# RD.net
KiCad netlist of a schematic drawn in Altium Designer
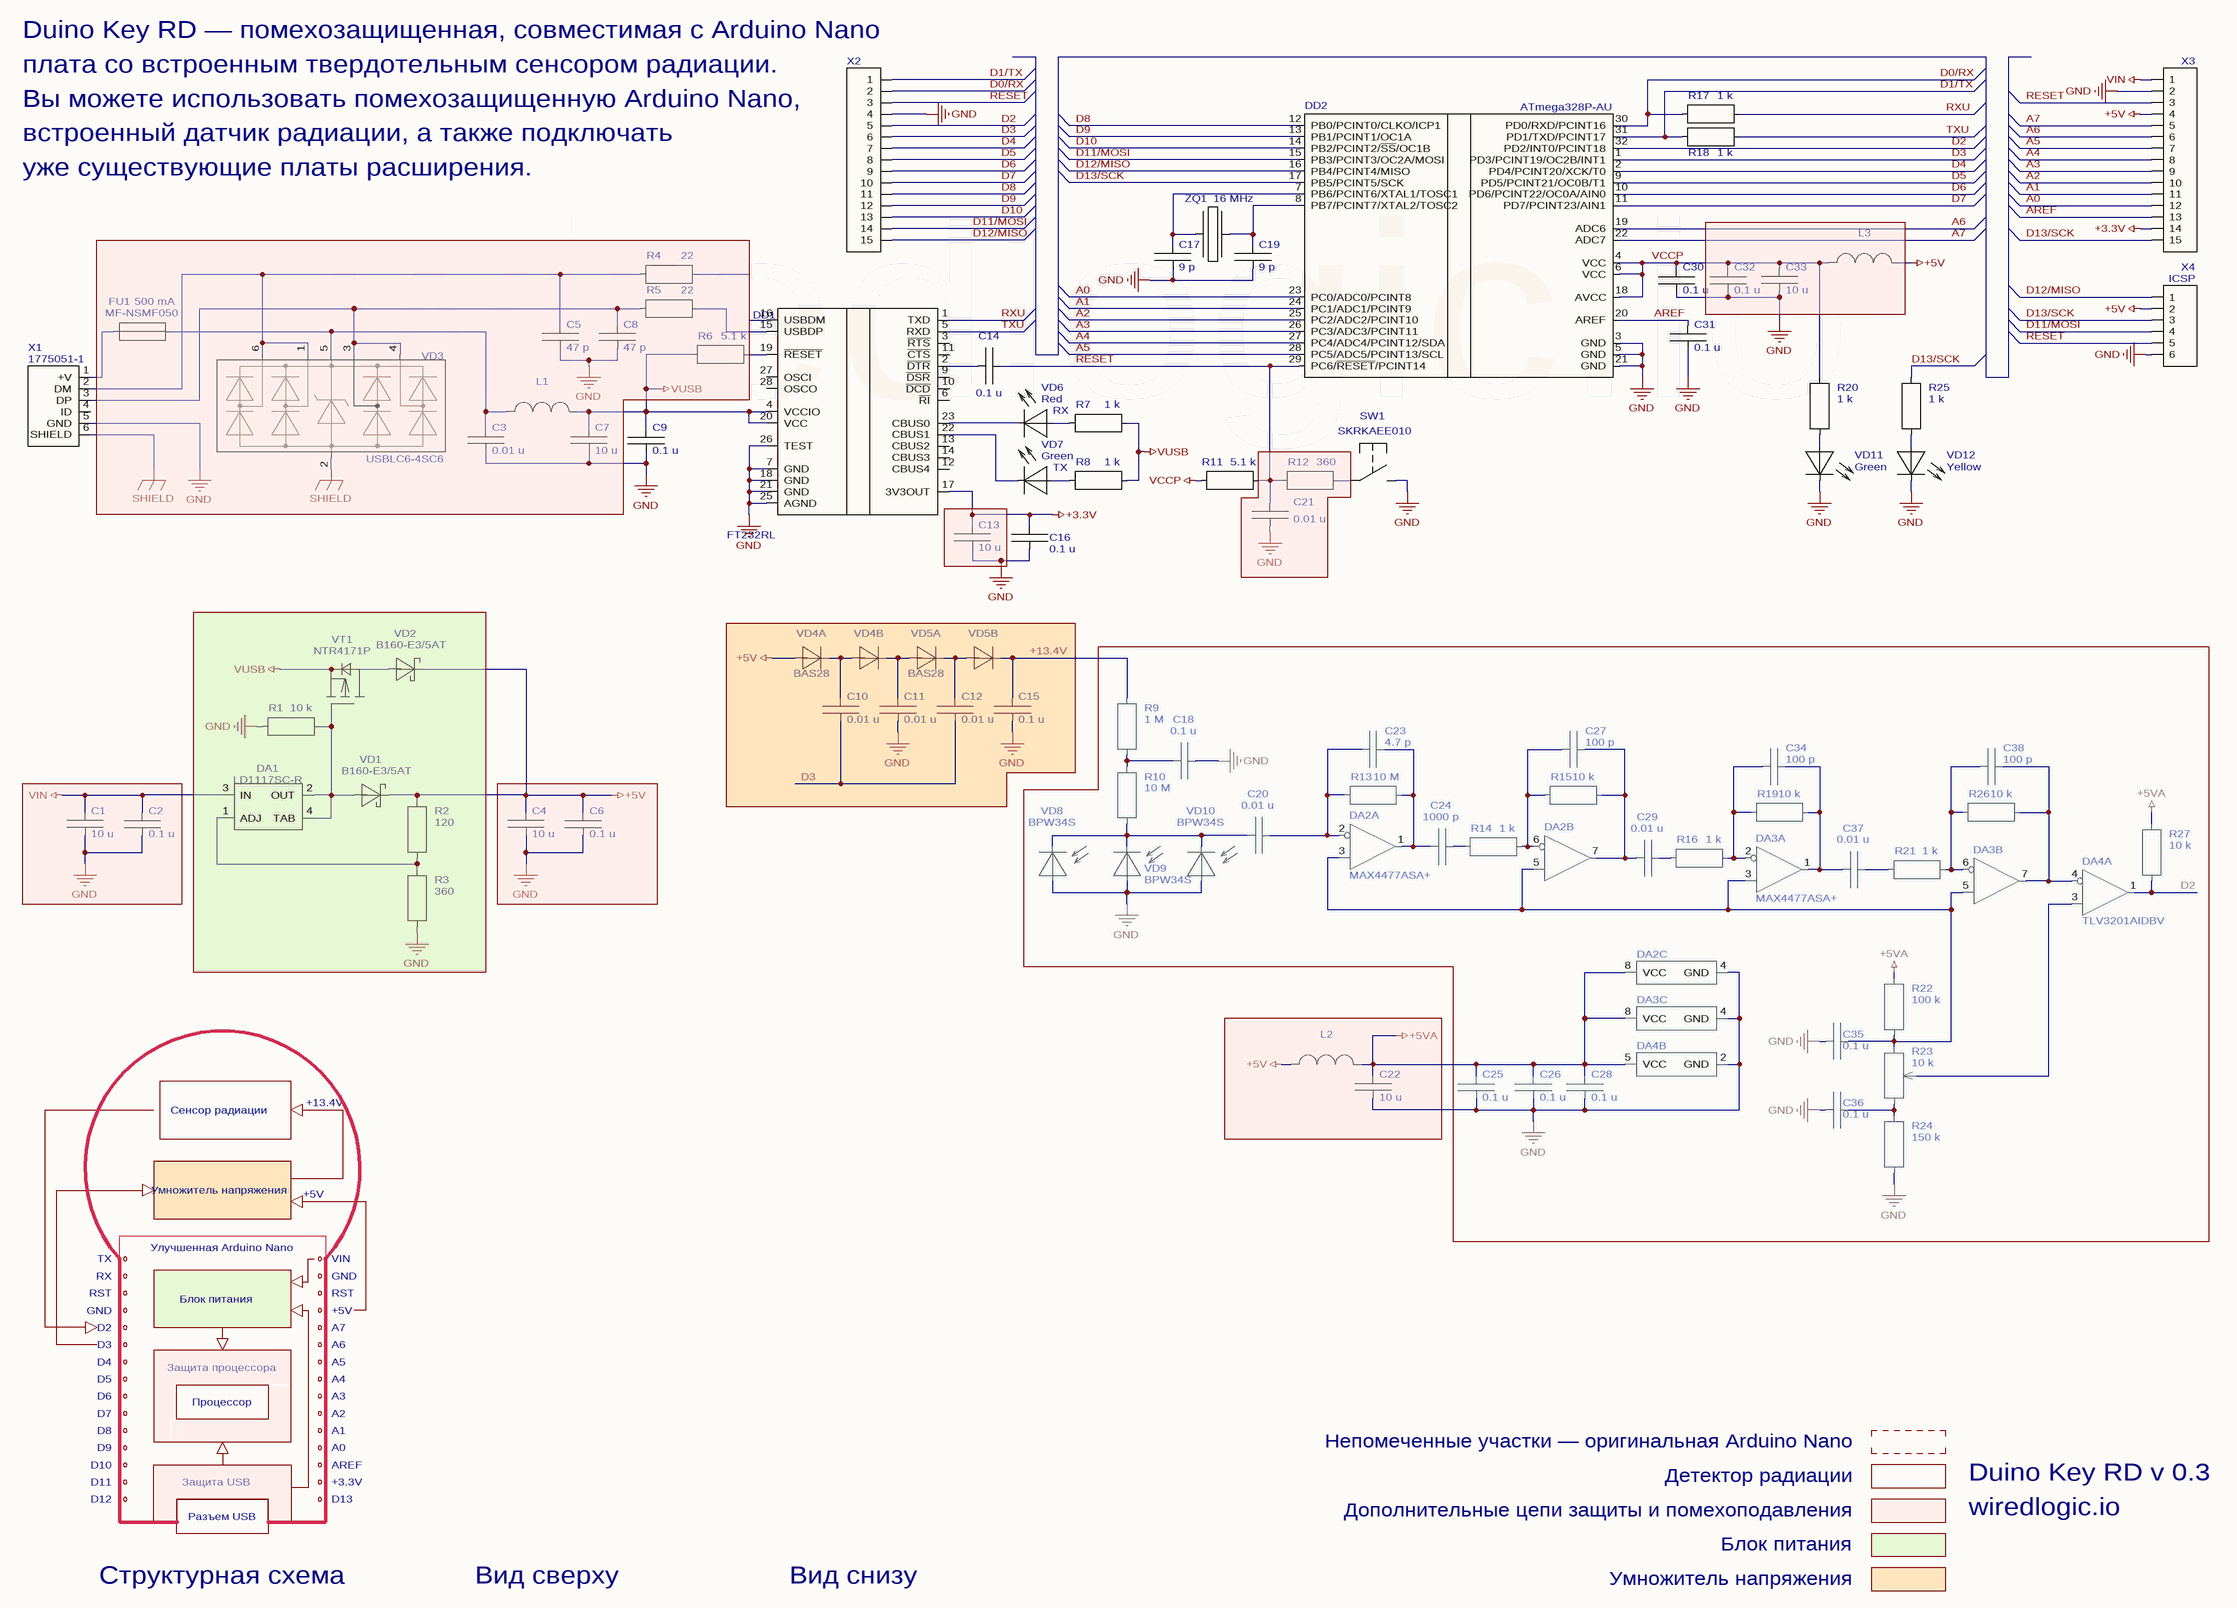
[diagram p0: RD.SchDoc]

(export (version "E")
  (design (tool "Eeschema 10.0.6"))
  (components
    (comp (ref "C1")
      (value "10 u")
      (footprint "C1206-1.6mm")
      (description "Ceramic capacitor")
      (fields (field (name "MANUFACTURER") "Yageo") (field (name "PART NUMBER") "CC1206KKX7R8BB106"))
      (libsource (lib "Sch") (part "C1206 10u"))
    )
    (comp (ref "C2")
      (value "0.1 u")
      (footprint "C0805-0.94mm")
      (description "Ceramic capacitor")
      (fields (field (name "MANUFACTURER") "AVX") (field (name "PART NUMBER") "08055C104KAT2A"))
      (libsource (lib "Sch") (part "C0805 0.1u"))
    )
    (comp (ref "C3")
      (value "0.01 u")
      (footprint "C0805-0.94mm")
      (description "Ceramic capacitor")
      (fields (field (name "MANUFACTURER") "AVX") (field (name "PART NUMBER") "08055C103KAT2A"))
      (libsource (lib "Sch") (part "C0805 0.01u"))
    )
    (comp (ref "C4")
      (value "10 u")
      (footprint "C1206-1.6mm")
      (description "Ceramic capacitor")
      (fields (field (name "MANUFACTURER") "Yageo") (field (name "PART NUMBER") "CC1206KKX7R8BB106"))
      (libsource (lib "Sch") (part "C1206 10u"))
    )
    (comp (ref "C5")
      (value "47 p")
      (footprint "C0805-0.94mm")
      (description "Ceramic capacitor")
      (fields (field (name "MANUFACTURER") "Kemet") (field (name "PART NUMBER") "C0805C470J5GACTU"))
      (libsource (lib "Sch") (part "C0805 47p"))
    )
    (comp (ref "C6")
      (value "0.1 u")
      (footprint "C0805-0.94mm")
      (description "Ceramic capacitor")
      (fields (field (name "MANUFACTURER") "AVX") (field (name "PART NUMBER") "08055C104KAT2A"))
      (libsource (lib "Sch") (part "C0805 0.1u"))
    )
    (comp (ref "C7")
      (value "10 u")
      (footprint "C1206-1.6mm")
      (description "Ceramic capacitor")
      (fields (field (name "MANUFACTURER") "Yageo") (field (name "PART NUMBER") "CC1206KKX7R8BB106"))
      (libsource (lib "Sch") (part "C1206 10u"))
    )
    (comp (ref "C8")
      (value "47 p")
      (footprint "C0805-0.94mm")
      (description "Ceramic capacitor")
      (fields (field (name "MANUFACTURER") "Kemet") (field (name "PART NUMBER") "C0805C470J5GACTU"))
      (libsource (lib "Sch") (part "C0805 47p"))
    )
    (comp (ref "C9")
      (value "0.1 u")
      (footprint "C0805-0.94mm")
      (description "Ceramic capacitor")
      (fields (field (name "MANUFACTURER") "AVX") (field (name "PART NUMBER") "08055C104KAT2A"))
      (libsource (lib "Sch") (part "C0805 0.1u"))
    )
    (comp (ref "C10")
      (value "0.01 u")
      (footprint "C0805-0.94mm")
      (description "Ceramic capacitor")
      (fields (field (name "MANUFACTURER") "AVX") (field (name "PART NUMBER") "08055C103KAT2A"))
      (libsource (lib "Sch") (part "C0805 0.01u"))
    )
    (comp (ref "C11")
      (value "0.01 u")
      (footprint "C0805-0.94mm")
      (description "Ceramic capacitor")
      (fields (field (name "MANUFACTURER") "AVX") (field (name "PART NUMBER") "08055C103KAT2A"))
      (libsource (lib "Sch") (part "C0805 0.01u"))
    )
    (comp (ref "C12")
      (value "0.01 u")
      (footprint "C0805-0.94mm")
      (description "Ceramic capacitor")
      (fields (field (name "MANUFACTURER") "AVX") (field (name "PART NUMBER") "08055C103KAT2A"))
      (libsource (lib "Sch") (part "C0805 0.01u"))
    )
    (comp (ref "C13")
      (value "10 u")
      (footprint "C1206-1.6mm")
      (description "Ceramic capacitor")
      (fields (field (name "MANUFACTURER") "Yageo") (field (name "PART NUMBER") "CC1206KKX7R8BB106"))
      (libsource (lib "Sch") (part "C1206 10u"))
    )
    (comp (ref "C14")
      (value "0.1 u")
      (footprint "C0805-0.94mm")
      (description "Ceramic capacitor")
      (fields (field (name "MANUFACTURER") "AVX") (field (name "PART NUMBER") "08055C104KAT2A"))
      (libsource (lib "Sch") (part "C0805 0.1u"))
    )
    (comp (ref "C15")
      (value "0.1 u")
      (footprint "C0805-0.94mm")
      (description "Ceramic capacitor")
      (fields (field (name "MANUFACTURER") "AVX") (field (name "PART NUMBER") "08055C104KAT2A"))
      (libsource (lib "Sch") (part "C0805 0.1u"))
    )
    (comp (ref "C16")
      (value "0.1 u")
      (footprint "C0805-0.94mm")
      (description "Ceramic capacitor")
      (fields (field (name "MANUFACTURER") "AVX") (field (name "PART NUMBER") "08055C104KAT2A"))
      (libsource (lib "Sch") (part "C0805 0.1u"))
    )
    (comp (ref "C17")
      (value "9 p")
      (footprint "C0805-0.94mm")
      (description "Ceramic capacitor")
      (fields (field (name "MANUFACTURER") "Yageo") (field (name "PART NUMBER") "CC0805DRNPO9BN9R0"))
      (libsource (lib "Sch") (part "C0805 9p"))
    )
    (comp (ref "C18")
      (value "0.1 u")
      (footprint "C0805-0.94mm")
      (description "Ceramic capacitor")
      (fields (field (name "MANUFACTURER") "AVX") (field (name "PART NUMBER") "08055C104KAT2A"))
      (libsource (lib "Sch") (part "C0805 0.1u"))
    )
    (comp (ref "C19")
      (value "9 p")
      (footprint "C0805-0.94mm")
      (description "Ceramic capacitor")
      (fields (field (name "MANUFACTURER") "Yageo") (field (name "PART NUMBER") "CC0805DRNPO9BN9R0"))
      (libsource (lib "Sch") (part "C0805 9p"))
    )
    (comp (ref "C20")
      (value "0.01 u")
      (footprint "C0805-0.94mm")
      (description "Ceramic capacitor")
      (fields (field (name "MANUFACTURER") "AVX") (field (name "PART NUMBER") "08055C103KAT2A"))
      (libsource (lib "Sch") (part "C0805 0.01u"))
    )
    (comp (ref "C21")
      (value "0.01 u")
      (footprint "C0805-0.94mm")
      (description "Ceramic capacitor")
      (fields (field (name "MANUFACTURER") "AVX") (field (name "PART NUMBER") "08055C103KAT2A"))
      (libsource (lib "Sch") (part "C0805 0.01u"))
    )
    (comp (ref "C22")
      (value "10 u")
      (footprint "C1206-1.6mm")
      (description "Ceramic capacitor")
      (fields (field (name "MANUFACTURER") "Yageo") (field (name "PART NUMBER") "CC1206KKX7R8BB106"))
      (libsource (lib "Sch") (part "C1206 10u"))
    )
    (comp (ref "C23")
      (value "4.7 p")
      (footprint "C0805-0.94mm")
      (description "Ceramic capacitor")
      (fields (field (name "MANUFACTURER") "Yageo") (field (name "PART NUMBER") "CC0805CRNPO9BN4R7"))
      (libsource (lib "Sch") (part "C0805 4.7p"))
    )
    (comp (ref "C24")
      (value "1000 p")
      (footprint "C0805-0.94mm")
      (description "Ceramic capacitor")
      (fields (field (name "MANUFACTURER") "Kemet") (field (name "PART NUMBER") "C0805C102K5RACTU"))
      (libsource (lib "Sch") (part "C0805 1000p"))
    )
    (comp (ref "C25")
      (value "0.1 u")
      (footprint "C0805-0.94mm")
      (description "Ceramic capacitor")
      (fields (field (name "MANUFACTURER") "AVX") (field (name "PART NUMBER") "08055C104KAT2A"))
      (libsource (lib "Sch") (part "C0805 0.1u"))
    )
    (comp (ref "C26")
      (value "0.1 u")
      (footprint "C0805-0.94mm")
      (description "Ceramic capacitor")
      (fields (field (name "MANUFACTURER") "AVX") (field (name "PART NUMBER") "08055C104KAT2A"))
      (libsource (lib "Sch") (part "C0805 0.1u"))
    )
    (comp (ref "C27")
      (value "100 p")
      (footprint "C0805-0.94mm")
      (description "Ceramic capacitor")
      (fields (field (name "MANUFACTURER") "Kemet") (field (name "PART NUMBER") "C0805C101J5GACTU"))
      (libsource (lib "Sch") (part "C0805 100p"))
    )
    (comp (ref "C28")
      (value "0.1 u")
      (footprint "C0805-0.94mm")
      (description "Ceramic capacitor")
      (fields (field (name "MANUFACTURER") "AVX") (field (name "PART NUMBER") "08055C104KAT2A"))
      (libsource (lib "Sch") (part "C0805 0.1u"))
    )
    (comp (ref "C29")
      (value "0.01 u")
      (footprint "C0805-0.94mm")
      (description "Ceramic capacitor")
      (fields (field (name "MANUFACTURER") "AVX") (field (name "PART NUMBER") "08055C103KAT2A"))
      (libsource (lib "Sch") (part "C0805 0.01u"))
    )
    (comp (ref "C30")
      (value "0.1 u")
      (footprint "C0805-0.94mm")
      (description "Ceramic capacitor")
      (fields (field (name "MANUFACTURER") "AVX") (field (name "PART NUMBER") "08055C104KAT2A"))
      (libsource (lib "Sch") (part "C0805 0.1u"))
    )
    (comp (ref "C31")
      (value "0.1 u")
      (footprint "C0805-0.94mm")
      (description "Ceramic capacitor")
      (fields (field (name "MANUFACTURER") "AVX") (field (name "PART NUMBER") "08055C104KAT2A"))
      (libsource (lib "Sch") (part "C0805 0.1u"))
    )
    (comp (ref "C32")
      (value "0.1 u")
      (footprint "C0805-0.94mm")
      (description "Ceramic capacitor")
      (fields (field (name "MANUFACTURER") "AVX") (field (name "PART NUMBER") "08055C104KAT2A"))
      (libsource (lib "Sch") (part "C0805 0.1u"))
    )
    (comp (ref "C33")
      (value "10 u")
      (footprint "C1206-1.6mm")
      (description "Ceramic capacitor")
      (fields (field (name "MANUFACTURER") "Yageo") (field (name "PART NUMBER") "CC1206KKX7R8BB106"))
      (libsource (lib "Sch") (part "C1206 10u"))
    )
    (comp (ref "C34")
      (value "100 p")
      (footprint "C0805-0.94mm")
      (description "Ceramic capacitor")
      (fields (field (name "MANUFACTURER") "Kemet") (field (name "PART NUMBER") "C0805C101J5GACTU"))
      (libsource (lib "Sch") (part "C0805 100p"))
    )
    (comp (ref "C35")
      (value "0.1 u")
      (footprint "C0805-0.94mm")
      (description "Ceramic capacitor")
      (fields (field (name "MANUFACTURER") "AVX") (field (name "PART NUMBER") "08055C104KAT2A"))
      (libsource (lib "Sch") (part "C0805 0.1u"))
    )
    (comp (ref "C36")
      (value "0.1 u")
      (footprint "C0805-0.94mm")
      (description "Ceramic capacitor")
      (fields (field (name "MANUFACTURER") "AVX") (field (name "PART NUMBER") "08055C104KAT2A"))
      (libsource (lib "Sch") (part "C0805 0.1u"))
    )
    (comp (ref "C37")
      (value "0.01 u")
      (footprint "C0805-0.94mm")
      (description "Ceramic capacitor")
      (fields (field (name "MANUFACTURER") "AVX") (field (name "PART NUMBER") "08055C103KAT2A"))
      (libsource (lib "Sch") (part "C0805 0.01u"))
    )
    (comp (ref "C38")
      (value "100 p")
      (footprint "C0805-0.94mm")
      (description "Ceramic capacitor")
      (fields (field (name "MANUFACTURER") "Kemet") (field (name "PART NUMBER") "C0805C101J5GACTU"))
      (libsource (lib "Sch") (part "C0805 100p"))
    )
    (comp (ref "DA1")
      (value "~")
      (footprint "SOT-223-LD1117SC-R")
      (description "Adjustable LDO")
      (fields (field (name "MANUFACTURER") "ST Microelectronics") (field (name "PART NUMBER") "LD1117SC-R"))
      (libsource (lib "Sch") (part "DA LD1117SC-R"))
    )
    (comp (ref "DA2")
      (value "~")
      (footprint "SOIC8-MAX4477ASA")
      (description "Operational amplifier")
      (fields (field (name "MANUFACTURER") "Maxim") (field (name "PART NUMBER") "MAX4477ASA+"))
      (libsource (lib "Sch") (part "DA MAX4477ASA+"))
    )
    (comp (ref "DA3")
      (value "~")
      (footprint "SOIC8-MAX4477ASA")
      (description "Operational amplifier")
      (fields (field (name "MANUFACTURER") "Maxim") (field (name "PART NUMBER") "MAX4477ASA+"))
      (libsource (lib "Sch") (part "DA MAX4477ASA+"))
    )
    (comp (ref "DA4")
      (value "~")
      (footprint "SOT23-5-TLV3201AIDBV")
      (description "Push-pull output comparator")
      (fields (field (name "MANUFACTURER") "TI") (field (name "PART NUMBER") "TLV3201AIDBV"))
      (libsource (lib "Sch") (part "DA TLV3201AIDBV"))
    )
    (comp (ref "DD1")
      (value "~")
      (footprint "SSOP-28-FT232RL")
      (description "USB to UART interface")
      (fields (field (name "MANUFACTURER") "FTDI") (field (name "PART NUMBER") "FT232RL"))
      (libsource (lib "Sch") (part "DD FT232RL"))
    )
    (comp (ref "DD2")
      (value "~")
      (footprint "TQFP32-ATmega328P-AU")
      (description "AVR Microcontroller")
      (fields (field (name "MANUFACTURER") "Atmel") (field (name "PART NUMBER") "ATmega328P-AU"))
      (libsource (lib "Sch") (part "DD ATmega328P-AU"))
    )
    (comp (ref "FU1")
      (value "500 mA")
      (footprint "FU-MF-NSMF050")
      (description "PTC resettable fuse")
      (fields (field (name "MANUFACTURER") "Bourns") (field (name "PART NUMBER") "MF-NSMF050"))
      (libsource (lib "Sch") (part "FU 0.5A"))
    )
    (comp (ref "L1")
      (value "~")
      (footprint "L-ILHB1206")
      (description "Multilayer ferrite bead")
      (fields (field (name "MANUFACTURER") "Vishay") (field (name "PART NUMBER") "ILHB1206ER601V"))
      (libsource (lib "Sch") (part "L ILHB1206ER601V"))
    )
    (comp (ref "L2")
      (value "~")
      (footprint "L-ILHB1206")
      (description "Multilayer ferrite bead")
      (fields (field (name "MANUFACTURER") "Vishay") (field (name "PART NUMBER") "ILHB1206ER601V"))
      (libsource (lib "Sch") (part "L ILHB1206ER601V"))
    )
    (comp (ref "L3")
      (value "~")
      (footprint "L-ILHB1206")
      (description "Multilayer ferrite bead")
      (fields (field (name "MANUFACTURER") "Vishay") (field (name "PART NUMBER") "ILHB1206ER601V"))
      (libsource (lib "Sch") (part "L ILHB1206ER601V"))
    )
    (comp (ref "R1")
      (value "10 k")
      (footprint "R0805-1-10k")
      (description "Thick film resistor")
      (fields (field (name "MANUFACTURER") "Yageo") (field (name "PART NUMBER") "RC0805FR-0710KL"))
      (libsource (lib "Sch") (part "R0805 10k"))
    )
    (comp (ref "R2")
      (value "120")
      (footprint "R0805-1-120")
      (description "Thick film resistor")
      (fields (field (name "MANUFACTURER") "Yageo") (field (name "PART NUMBER") "RC0805FR-07120RL"))
      (libsource (lib "Sch") (part "R0805 120"))
    )
    (comp (ref "R3")
      (value "360")
      (footprint "R0805-1-360")
      (description "Thick film resistor")
      (fields (field (name "MANUFACTURER") "Yageo") (field (name "PART NUMBER") "RC0805FR-07360RL"))
      (libsource (lib "Sch") (part "R0805 360"))
    )
    (comp (ref "R4")
      (value "22")
      (footprint "R0805-1-22")
      (description "Thick film resistor")
      (fields (field (name "MANUFACTURER") "Yageo") (field (name "PART NUMBER") "RC0805FR-0722RL"))
      (libsource (lib "Sch") (part "R0805 22"))
    )
    (comp (ref "R5")
      (value "22")
      (footprint "R0805-1-22")
      (description "Thick film resistor")
      (fields (field (name "MANUFACTURER") "Yageo") (field (name "PART NUMBER") "RC0805FR-0722RL"))
      (libsource (lib "Sch") (part "R0805 22"))
    )
    (comp (ref "R6")
      (value "5.1 k")
      (footprint "R0805-1-5.1k")
      (description "Thick film resistor")
      (fields (field (name "MANUFACTURER") "Yageo") (field (name "PART NUMBER") "RC0805FR-075K1L"))
      (libsource (lib "Sch") (part "R0805 5.1k"))
    )
    (comp (ref "R7")
      (value "1 k")
      (footprint "R0805-1-1k")
      (description "Thick film resistor")
      (fields (field (name "MANUFACTURER") "Yageo") (field (name "PART NUMBER") "RC0805FR-071KL"))
      (libsource (lib "Sch") (part "R0805 1k"))
    )
    (comp (ref "R8")
      (value "1 k")
      (footprint "R0805-1-1k")
      (description "Thick film resistor")
      (fields (field (name "MANUFACTURER") "Yageo") (field (name "PART NUMBER") "RC0805FR-071KL"))
      (libsource (lib "Sch") (part "R0805 1k"))
    )
    (comp (ref "R9")
      (value "1 M")
      (footprint "R0805-1-1M")
      (description "Thick film resistor")
      (fields (field (name "MANUFACTURER") "Yageo") (field (name "PART NUMBER") "RC0805FR-071ML"))
      (libsource (lib "Sch") (part "R0805 1M"))
    )
    (comp (ref "R10")
      (value "10 M")
      (footprint "R0805-1-10M")
      (description "Thick film resistor")
      (fields (field (name "MANUFACTURER") "Yageo") (field (name "PART NUMBER") "RC0805FR-0710ML"))
      (libsource (lib "Sch") (part "R0805 10M"))
    )
    (comp (ref "R11")
      (value "5.1 k")
      (footprint "R0805-1-5.1k")
      (description "Thick film resistor")
      (fields (field (name "MANUFACTURER") "Yageo") (field (name "PART NUMBER") "RC0805FR-075K1L"))
      (libsource (lib "Sch") (part "R0805 5.1k"))
    )
    (comp (ref "R12")
      (value "360")
      (footprint "R0805-1-360")
      (description "Thick film resistor")
      (fields (field (name "MANUFACTURER") "Yageo") (field (name "PART NUMBER") "RC0805FR-07360RL"))
      (libsource (lib "Sch") (part "R0805 360"))
    )
    (comp (ref "R13")
      (value "10 M")
      (footprint "R0805-1-10M")
      (description "Thick film resistor")
      (fields (field (name "MANUFACTURER") "Yageo") (field (name "PART NUMBER") "RC0805FR-0710ML"))
      (libsource (lib "Sch") (part "R0805 10M"))
    )
    (comp (ref "R14")
      (value "1 k")
      (footprint "R0805-1-1k")
      (description "Thick film resistor")
      (fields (field (name "MANUFACTURER") "Yageo") (field (name "PART NUMBER") "RC0805FR-071KL"))
      (libsource (lib "Sch") (part "R0805 1k"))
    )
    (comp (ref "R15")
      (value "10 k")
      (footprint "R0805-1-10k")
      (description "Thick film resistor")
      (fields (field (name "MANUFACTURER") "Yageo") (field (name "PART NUMBER") "RC0805FR-0710KL"))
      (libsource (lib "Sch") (part "R0805 10k"))
    )
    (comp (ref "R16")
      (value "1 k")
      (footprint "R0805-1-1k")
      (description "Thick film resistor")
      (fields (field (name "MANUFACTURER") "Yageo") (field (name "PART NUMBER") "RC0805FR-071KL"))
      (libsource (lib "Sch") (part "R0805 1k"))
    )
    (comp (ref "R17")
      (value "1 k")
      (footprint "R0805-1-1k")
      (description "Thick film resistor")
      (fields (field (name "MANUFACTURER") "Yageo") (field (name "PART NUMBER") "RC0805FR-071KL"))
      (libsource (lib "Sch") (part "R0805 1k"))
    )
    (comp (ref "R18")
      (value "1 k")
      (footprint "R0805-1-1k")
      (description "Thick film resistor")
      (fields (field (name "MANUFACTURER") "Yageo") (field (name "PART NUMBER") "RC0805FR-071KL"))
      (libsource (lib "Sch") (part "R0805 1k"))
    )
    (comp (ref "R19")
      (value "10 k")
      (footprint "R0805-1-10k")
      (description "Thick film resistor")
      (fields (field (name "MANUFACTURER") "Yageo") (field (name "PART NUMBER") "RC0805FR-0710KL"))
      (libsource (lib "Sch") (part "R0805 10k"))
    )
    (comp (ref "R20")
      (value "1 k")
      (footprint "R0805-1-1k")
      (description "Thick film resistor")
      (fields (field (name "MANUFACTURER") "Yageo") (field (name "PART NUMBER") "RC0805FR-071KL"))
      (libsource (lib "Sch") (part "R0805 1k"))
    )
    (comp (ref "R21")
      (value "1 k")
      (footprint "R0805-1-1k")
      (description "Thick film resistor")
      (fields (field (name "MANUFACTURER") "Yageo") (field (name "PART NUMBER") "RC0805FR-071KL"))
      (libsource (lib "Sch") (part "R0805 1k"))
    )
    (comp (ref "R22")
      (value "100 k")
      (footprint "R0805-1-100k")
      (description "Thick film resistor")
      (fields (field (name "MANUFACTURER") "Yageo") (field (name "PART NUMBER") "RC0805FR-07100KL"))
      (libsource (lib "Sch") (part "R0805 100k"))
    )
    (comp (ref "R23")
      (value "10 k")
      (footprint "R Trim 10k 3319")
      (description "Trimming resistor")
      (fields (field (name "MANUFACTURER") "Bourns") (field (name "PART NUMBER") "3319P-1-103"))
      (libsource (lib "Sch") (part "R Trim 10k 3319"))
    )
    (comp (ref "R24")
      (value "150 k")
      (footprint "R0805-1-150k")
      (description "Thick film resistor")
      (fields (field (name "MANUFACTURER") "Yageo") (field (name "PART NUMBER") "RC0805FR-07150KL"))
      (libsource (lib "Sch") (part "R0805 150k"))
    )
    (comp (ref "R25")
      (value "1 k")
      (footprint "R0805-1-1k")
      (description "Thick film resistor")
      (fields (field (name "MANUFACTURER") "Yageo") (field (name "PART NUMBER") "RC0805FR-071KL"))
      (libsource (lib "Sch") (part "R0805 1k"))
    )
    (comp (ref "R26")
      (value "10 k")
      (footprint "R0805-1-10k")
      (description "Thick film resistor")
      (fields (field (name "MANUFACTURER") "Yageo") (field (name "PART NUMBER") "RC0805FR-0710KL"))
      (libsource (lib "Sch") (part "R0805 10k"))
    )
    (comp (ref "R27")
      (value "10 k")
      (footprint "R0805-1-10k")
      (description "Thick film resistor")
      (fields (field (name "MANUFACTURER") "Yageo") (field (name "PART NUMBER") "RC0805FR-0710KL"))
      (libsource (lib "Sch") (part "R0805 10k"))
    )
    (comp (ref "SW1")
      (value "~")
      (footprint "SW SKRKAEE010")
      (description "Button")
      (fields (field (name "MANUFACTURER") "ALPS") (field (name "PART NUMBER") "SKRKAEE010"))
      (libsource (lib "Sch") (part "SW SKRKAEE010"))
    )
    (comp (ref "VD1")
      (value "~")
      (footprint "DO-214AC-B160")
      (description "Shottky diode")
      (fields (field (name "MANUFACTURER") "Vishay") (field (name "PART NUMBER") "B160-E3/5AT"))
      (libsource (lib "Sch") (part "VD B160-E3/5AT"))
    )
    (comp (ref "VD2")
      (value "~")
      (footprint "DO-214AC-B160")
      (description "Shottky diode")
      (fields (field (name "MANUFACTURER") "Vishay") (field (name "PART NUMBER") "B160-E3/5AT"))
      (libsource (lib "Sch") (part "VD B160-E3/5AT"))
    )
    (comp (ref "VD3")
      (value "~")
      (footprint "SOT23-6-USBLC6-4")
      (description "ESD protection")
      (fields (field (name "MANUFACTURER") "ST") (field (name "PART NUMBER") "USBLC6-4SC6"))
      (libsource (lib "Sch") (part "VD USBLC6-4SC6 One side"))
    )
    (comp (ref "VD4")
      (value "~")
      (footprint "SOT143B")
      (description "Double diode")
      (fields (field (name "MANUFACTURER") "Nexperia") (field (name "PART NUMBER") "BAS28"))
      (libsource (lib "Sch") (part "VD BAS28"))
    )
    (comp (ref "VD5")
      (value "~")
      (footprint "SOT143B")
      (description "Double diode")
      (fields (field (name "MANUFACTURER") "Nexperia") (field (name "PART NUMBER") "BAS28"))
      (libsource (lib "Sch") (part "VD BAS28"))
    )
    (comp (ref "VD6")
      (value "Red")
      (footprint "VD LED 0805")
      (description "LED")
      (fields (field (name "MANUFACTURER") "Lite-On") (field (name "PART NUMBER") "LTST-C171KRKT"))
      (libsource (lib "Sch") (part "VD LED 0805 Red"))
    )
    (comp (ref "VD7")
      (value "Green")
      (footprint "VD LED 0805")
      (description "LED")
      (fields (field (name "MANUFACTURER") "Lite-On") (field (name "PART NUMBER") "LTST-C171GKT"))
      (libsource (lib "Sch") (part "VD LED 0805 Green"))
    )
    (comp (ref "VD8")
      (value "~")
      (footprint "VD BPW34S")
      (description "Photodiode")
      (fields (field (name "MANUFACTURER") "Vishay") (field (name "PART NUMBER") "BPW34S"))
      (libsource (lib "Sch") (part "VD BPW34S"))
    )
    (comp (ref "VD9")
      (value "~")
      (footprint "VD BPW34S")
      (description "Photodiode")
      (fields (field (name "MANUFACTURER") "Vishay") (field (name "PART NUMBER") "BPW34S"))
      (libsource (lib "Sch") (part "VD BPW34S"))
    )
    (comp (ref "VD10")
      (value "~")
      (footprint "VD BPW34S")
      (description "Photodiode")
      (fields (field (name "MANUFACTURER") "Vishay") (field (name "PART NUMBER") "BPW34S"))
      (libsource (lib "Sch") (part "VD BPW34S"))
    )
    (comp (ref "VD11")
      (value "Green")
      (footprint "VD LED 0805")
      (description "LED")
      (fields (field (name "MANUFACTURER") "Lite-On") (field (name "PART NUMBER") "LTST-C171GKT"))
      (libsource (lib "Sch") (part "VD LED 0805 Green"))
    )
    (comp (ref "VD12")
      (value "Yellow")
      (footprint "VD LED 0805")
      (description "LED")
      (fields (field (name "MANUFACTURER") "Lite-On") (field (name "PART NUMBER") "LTST-C171KSKT"))
      (libsource (lib "Sch") (part "VD LED 0805 Yellow"))
    )
    (comp (ref "VT1")
      (value "~")
      (footprint "SOT23-NTR4171P")
      (description "P-channel MOSFET")
      (fields (field (name "MANUFACTURER") "ON Semiconductor") (field (name "PART NUMBER") "NTR4171P"))
      (libsource (lib "Sch") (part "VT NTR4171P"))
    )
    (comp (ref "X1")
      (value "~")
      (footprint "X USB 1775051-1")
      (description "USB connector")
      (fields (field (name "MANUFACTURER") "TE") (field (name "PART NUMBER") "1775051-1"))
      (libsource (lib "Sch") (part "X USB 1775051-1"))
    )
    (comp (ref "X2")
      (value "~")
      (footprint "X PLS-15")
      (description "PLS connector")
      (fields (field (name "MANUFACTURER") "Molex") (field (name "PART NUMBER") "22-28-4150"))
      (libsource (lib "") (part "X PLS-15_1"))
    )
    (comp (ref "X3")
      (value "~")
      (footprint "X PLS-15")
      (description "PLS connector")
      (fields (field (name "MANUFACTURER") "Molex") (field (name "PART NUMBER") "22-28-4150"))
      (libsource (lib "Sch") (part "X PLS-15"))
    )
    (comp (ref "X4")
      (value "~")
      (footprint "X PLD-6")
      (description "PLD connector")
      (fields (field (name "MANUFACTURER") "TE Connectivity") (field (name "PART NUMBER") "5-146254-3"))
      (libsource (lib "Sch") (part "X PLD-6"))
    )
    (comp (ref "ZQ1")
      (value "16 MHz")
      (footprint "ZQ TSX-3225 16.0000MF09Z-AC3")
      (description "Crystal")
      (fields
        (field (name "MANUFACTURER") "Citizen")
        (field (name "PART NUMBER") "TSX-3225 16.0000MF09Z-AC3")
      )
      (libsource (lib "Sch") (part "ZQ TSX-3225 16.0000MF09Z-AC3"))
    )
  )
  (nets
    (net (code "1") (name "+3.3V") (class "Default")
      (node (ref "C13") (pin "1") (pintype "passive"))
      (node (ref "C16") (pin "2") (pintype "passive"))
      (node (ref "DD1") (pin "17") (pinfunction "3V3OUT_17") (pintype "passive"))
      (node (ref "X3") (pin "14") (pinfunction "14_14") (pintype "passive"))
    )
    (net (code "2") (name "+5V") (class "Default")
      (node (ref "C4") (pin "1") (pintype "passive"))
      (node (ref "C6") (pin "2") (pintype "passive"))
      (node (ref "L2") (pin "2") (pintype "passive"))
      (node (ref "L3") (pin "1") (pintype "passive"))
      (node (ref "R2") (pin "1") (pinfunction "1_1") (pintype "passive"))
      (node (ref "VD1") (pin "1") (pintype "passive"))
      (node (ref "VD2") (pin "1") (pintype "passive"))
      (node (ref "VD4") (pin "4") (pinfunction "4_4") (pintype "passive"))
      (node (ref "X3") (pin "4") (pinfunction "4_4") (pintype "passive"))
      (node (ref "X4") (pin "2") (pinfunction "2_2") (pintype "passive"))
    )
    (net (code "3") (name "+5VA") (class "Default")
      (node (ref "C22") (pin "1") (pintype "passive"))
      (node (ref "C25") (pin "2") (pintype "passive"))
      (node (ref "C26") (pin "2") (pintype "passive"))
      (node (ref "C28") (pin "2") (pintype "passive"))
      (node (ref "DA2") (pin "8") (pinfunction "VCC_8") (pintype "power_in"))
      (node (ref "DA3") (pin "8") (pinfunction "VCC_8") (pintype "power_in"))
      (node (ref "DA4") (pin "5") (pinfunction "VCC_5") (pintype "power_in"))
      (node (ref "L2") (pin "1") (pintype "passive"))
      (node (ref "R22") (pin "1") (pinfunction "1_1") (pintype "passive"))
      (node (ref "R27") (pin "2") (pinfunction "2_2") (pintype "passive"))
    )
    (net (code "4") (name "/+13.4V") (class "Default")
      (node (ref "C15") (pin "2") (pintype "passive"))
      (node (ref "R9") (pin "1") (pinfunction "1_1") (pintype "passive"))
      (node (ref "VD5") (pin "2") (pinfunction "2_2") (pintype "passive"))
    )
    (net (code "5") (name "/A0") (class "Default")
      (node (ref "DD2") (pin "23") (pinfunction "PC0/ADC0/PCINT8_23") (pintype "passive"))
      (node (ref "X3") (pin "12") (pinfunction "12_12") (pintype "passive"))
    )
    (net (code "6") (name "/A1") (class "Default")
      (node (ref "DD2") (pin "24") (pinfunction "PC1/ADC1/PCINT9_24") (pintype "passive"))
      (node (ref "X3") (pin "11") (pinfunction "11_11") (pintype "passive"))
    )
    (net (code "7") (name "/A2") (class "Default")
      (node (ref "DD2") (pin "25") (pinfunction "PC2/ADC2/PCINT10_25") (pintype "passive"))
      (node (ref "X3") (pin "10") (pinfunction "10_10") (pintype "passive"))
    )
    (net (code "8") (name "/A3") (class "Default")
      (node (ref "DD2") (pin "26") (pinfunction "PC3/ADC3/PCINT11_26") (pintype "passive"))
      (node (ref "X3") (pin "9") (pinfunction "9_9") (pintype "passive"))
    )
    (net (code "9") (name "/A4") (class "Default")
      (node (ref "DD2") (pin "27") (pinfunction "PC4/ADC4/PCINT12/SDA_27") (pintype "passive"))
      (node (ref "X3") (pin "8") (pinfunction "8_8") (pintype "passive"))
    )
    (net (code "10") (name "/A5") (class "Default")
      (node (ref "DD2") (pin "28") (pinfunction "PC5/ADC5/PCINT13/SCL_28") (pintype "passive"))
      (node (ref "X3") (pin "7") (pinfunction "7_7") (pintype "passive"))
    )
    (net (code "11") (name "/A6") (class "Default")
      (node (ref "DD2") (pin "19") (pinfunction "ADC6_19") (pintype "passive"))
      (node (ref "X3") (pin "6") (pinfunction "6_6") (pintype "passive"))
    )
    (net (code "12") (name "/A7") (class "Default")
      (node (ref "DD2") (pin "22") (pinfunction "ADC7_22") (pintype "passive"))
      (node (ref "X3") (pin "5") (pinfunction "5_5") (pintype "passive"))
    )
    (net (code "13") (name "/AREF") (class "Default")
      (node (ref "C31") (pin "2") (pintype "passive"))
      (node (ref "DD2") (pin "20") (pinfunction "AREF_20") (pintype "passive"))
      (node (ref "X3") (pin "13") (pinfunction "13_13") (pintype "passive"))
    )
    (net (code "14") (name "/D0{slash}RX") (class "Default")
      (node (ref "DD2") (pin "30") (pinfunction "PD0/RXD/PCINT16_30") (pintype "passive"))
      (node (ref "R17") (pin "1") (pinfunction "1_1") (pintype "passive"))
      (node (ref "X2") (pin "2") (pinfunction "2_2") (pintype "passive"))
    )
    (net (code "15") (name "/D1{slash}TX") (class "Default")
      (node (ref "DD2") (pin "31") (pinfunction "PD1/TXD/PCINT17_31") (pintype "passive"))
      (node (ref "R18") (pin "1") (pinfunction "1_1") (pintype "passive"))
      (node (ref "X2") (pin "1") (pinfunction "1_1") (pintype "passive"))
    )
    (net (code "16") (name "/D2") (class "Default")
      (node (ref "DA4") (pin "1") (pinfunction "OUT_1") (pintype "passive"))
      (node (ref "DD2") (pin "32") (pinfunction "PD2/INT0/PCINT18_32") (pintype "passive"))
      (node (ref "R27") (pin "1") (pinfunction "1_1") (pintype "passive"))
      (node (ref "X2") (pin "5") (pinfunction "5_5") (pintype "passive"))
    )
    (net (code "17") (name "/D3") (class "Default")
      (node (ref "C10") (pin "1") (pintype "passive"))
      (node (ref "C12") (pin "1") (pintype "passive"))
      (node (ref "DD2") (pin "1") (pinfunction "PD3/PCINT19/OC2B/INT1_1") (pintype "passive"))
      (node (ref "X2") (pin "6") (pinfunction "6_6") (pintype "passive"))
    )
    (net (code "18") (name "/D4") (class "Default")
      (node (ref "DD2") (pin "2") (pinfunction "PD4/PCINT20/XCK/T0_2") (pintype "passive"))
      (node (ref "X2") (pin "7") (pinfunction "7_7") (pintype "passive"))
    )
    (net (code "19") (name "/D5") (class "Default")
      (node (ref "DD2") (pin "9") (pinfunction "PD5/PCINT21/OC0B/T1_9") (pintype "passive"))
      (node (ref "X2") (pin "8") (pinfunction "8_8") (pintype "passive"))
    )
    (net (code "20") (name "/D6") (class "Default")
      (node (ref "DD2") (pin "10") (pinfunction "PD6/PCINT22/OC0A/AIN0_10") (pintype "passive"))
      (node (ref "X2") (pin "9") (pinfunction "9_9") (pintype "passive"))
    )
    (net (code "21") (name "/D7") (class "Default")
      (node (ref "DD2") (pin "11") (pinfunction "PD7/PCINT23/AIN1_11") (pintype "passive"))
      (node (ref "X2") (pin "10") (pinfunction "10_10") (pintype "passive"))
    )
    (net (code "22") (name "/D8") (class "Default")
      (node (ref "DD2") (pin "12") (pinfunction "PB0/PCINT0/CLKO/ICP1_12") (pintype "passive"))
      (node (ref "X2") (pin "11") (pinfunction "11_11") (pintype "passive"))
    )
    (net (code "23") (name "/D9") (class "Default")
      (node (ref "DD2") (pin "13") (pinfunction "PB1/PCINT1/OC1A_13") (pintype "passive"))
      (node (ref "X2") (pin "12") (pinfunction "12_12") (pintype "passive"))
    )
    (net (code "24") (name "/D10") (class "Default")
      (node (ref "DD2") (pin "14") (pinfunction "PB2/PCINT2/~{SS}/OC1B_14") (pintype "passive"))
      (node (ref "X2") (pin "13") (pinfunction "13_13") (pintype "passive"))
    )
    (net (code "25") (name "/D11{slash}MOSI") (class "Default")
      (node (ref "DD2") (pin "15") (pinfunction "PB3/PCINT3/OC2A/MOSI_15") (pintype "passive"))
      (node (ref "X2") (pin "14") (pinfunction "14_14") (pintype "passive"))
      (node (ref "X4") (pin "4") (pinfunction "4_4") (pintype "passive"))
    )
    (net (code "26") (name "/D12{slash}MISO") (class "Default")
      (node (ref "DD2") (pin "16") (pinfunction "PB4/PCINT4/MISO_16") (pintype "passive"))
      (node (ref "X2") (pin "15") (pinfunction "15_15") (pintype "passive"))
      (node (ref "X4") (pin "1") (pinfunction "1_1") (pintype "passive"))
    )
    (net (code "27") (name "/D13{slash}SCK") (class "Default")
      (node (ref "DD2") (pin "17") (pinfunction "PB5/PCINT5/SCK_17") (pintype "passive"))
      (node (ref "R25") (pin "2") (pinfunction "2_2") (pintype "passive"))
      (node (ref "X3") (pin "15") (pinfunction "15_15") (pintype "passive"))
      (node (ref "X4") (pin "3") (pinfunction "3_3") (pintype "passive"))
    )
    (net (code "28") (name "/RESET") (class "Default")
      (node (ref "C14") (pin "1") (pintype "passive"))
      (node (ref "C21") (pin "2") (pintype "passive"))
      (node (ref "DD2") (pin "29") (pinfunction "PC6/~{RESET}/PCINT14_29") (pintype "passive"))
      (node (ref "R11") (pin "2") (pinfunction "2_2") (pintype "passive"))
      (node (ref "R12") (pin "1") (pinfunction "1_1") (pintype "passive"))
      (node (ref "X2") (pin "3") (pinfunction "3_3") (pintype "passive"))
      (node (ref "X3") (pin "3") (pinfunction "3_3") (pintype "passive"))
      (node (ref "X4") (pin "5") (pinfunction "5_5") (pintype "passive"))
    )
    (net (code "29") (name "/RXU") (class "Default")
      (node (ref "DD1") (pin "1") (pinfunction "TXD_1") (pintype "passive"))
      (node (ref "R17") (pin "2") (pinfunction "2_2") (pintype "passive"))
    )
    (net (code "30") (name "/TXU") (class "Default")
      (node (ref "DD1") (pin "5") (pinfunction "RXD_5") (pintype "passive"))
      (node (ref "R18") (pin "2") (pinfunction "2_2") (pintype "passive"))
    )
    (net (code "31") (name "GND") (class "Default")
      (node (ref "C1") (pin "2") (pintype "passive"))
      (node (ref "C11") (pin "1") (pintype "passive"))
      (node (ref "C13") (pin "2") (pintype "passive"))
      (node (ref "C15") (pin "1") (pintype "passive"))
      (node (ref "C16") (pin "1") (pintype "passive"))
      (node (ref "C17") (pin "2") (pintype "passive"))
      (node (ref "C18") (pin "2") (pintype "passive"))
      (node (ref "C19") (pin "2") (pintype "passive"))
      (node (ref "C2") (pin "1") (pintype "passive"))
      (node (ref "C21") (pin "1") (pintype "passive"))
      (node (ref "C22") (pin "2") (pintype "passive"))
      (node (ref "C25") (pin "1") (pintype "passive"))
      (node (ref "C26") (pin "1") (pintype "passive"))
      (node (ref "C28") (pin "1") (pintype "passive"))
      (node (ref "C3") (pin "2") (pintype "passive"))
      (node (ref "C30") (pin "1") (pintype "passive"))
      (node (ref "C31") (pin "1") (pintype "passive"))
      (node (ref "C32") (pin "1") (pintype "passive"))
      (node (ref "C33") (pin "2") (pintype "passive"))
      (node (ref "C35") (pin "1") (pintype "passive"))
      (node (ref "C36") (pin "1") (pintype "passive"))
      (node (ref "C4") (pin "2") (pintype "passive"))
      (node (ref "C5") (pin "2") (pintype "passive"))
      (node (ref "C6") (pin "1") (pintype "passive"))
      (node (ref "C7") (pin "2") (pintype "passive"))
      (node (ref "C8") (pin "2") (pintype "passive"))
      (node (ref "C9") (pin "1") (pintype "passive"))
      (node (ref "DA2") (pin "4") (pinfunction "GND_4") (pintype "power_in"))
      (node (ref "DA3") (pin "4") (pinfunction "GND_4") (pintype "power_in"))
      (node (ref "DA4") (pin "2") (pinfunction "GND_2") (pintype "power_in"))
      (node (ref "DD1") (pin "18") (pinfunction "GND_18") (pintype "passive"))
      (node (ref "DD1") (pin "21") (pinfunction "GND_21") (pintype "passive"))
      (node (ref "DD1") (pin "25") (pinfunction "AGND_25") (pintype "passive"))
      (node (ref "DD1") (pin "26") (pinfunction "TEST_26") (pintype "passive"))
      (node (ref "DD1") (pin "7") (pinfunction "GND_7") (pintype "passive"))
      (node (ref "DD2") (pin "21") (pinfunction "GND_21") (pintype "passive"))
      (node (ref "DD2") (pin "3") (pinfunction "GND_3") (pintype "passive"))
      (node (ref "DD2") (pin "5") (pinfunction "GND_5") (pintype "passive"))
      (node (ref "R1") (pin "1") (pinfunction "1_1") (pintype "passive"))
      (node (ref "R24") (pin "2") (pinfunction "2_2") (pintype "passive"))
      (node (ref "R3") (pin "2") (pinfunction "2_2") (pintype "passive"))
      (node (ref "SW1") (pin "1") (pintype "passive"))
      (node (ref "VD10") (pin "2") (pinfunction "A_2") (pintype "passive"))
      (node (ref "VD11") (pin "1") (pinfunction "K_1") (pintype "passive"))
      (node (ref "VD12") (pin "1") (pinfunction "K_1") (pintype "passive"))
      (node (ref "VD8") (pin "2") (pinfunction "A_2") (pintype "passive"))
      (node (ref "VD9") (pin "2") (pinfunction "A_2") (pintype "passive"))
      (node (ref "X1") (pin "5") (pinfunction "GND_5") (pintype "passive"))
      (node (ref "X2") (pin "4") (pinfunction "4_4") (pintype "passive"))
      (node (ref "X3") (pin "2") (pinfunction "2_2") (pintype "passive"))
      (node (ref "X4") (pin "6") (pinfunction "6_6") (pintype "passive"))
    )
    (net (code "32") (name "Net-(C3-Pad1)") (class "Default")
      (node (ref "C3") (pin "1") (pintype "passive"))
      (node (ref "FU1") (pin "2") (pinfunction "2_2") (pintype "passive"))
      (node (ref "L1") (pin "2") (pintype "passive"))
      (node (ref "VD3") (pin "5") (pintype "passive"))
    )
    (net (code "33") (name "Net-(C10-Pad2)") (class "Default")
      (node (ref "C10") (pin "2") (pintype "passive"))
      (node (ref "VD4") (pin "1") (pinfunction "1_1") (pintype "passive"))
      (node (ref "VD4") (pin "3") (pinfunction "3_3") (pintype "passive"))
    )
    (net (code "34") (name "Net-(C11-Pad2)") (class "Default")
      (node (ref "C11") (pin "2") (pintype "passive"))
      (node (ref "VD4") (pin "2") (pinfunction "2_2") (pintype "passive"))
      (node (ref "VD5") (pin "4") (pinfunction "4_4") (pintype "passive"))
    )
    (net (code "35") (name "Net-(C12-Pad2)") (class "Default")
      (node (ref "C12") (pin "2") (pintype "passive"))
      (node (ref "VD5") (pin "1") (pinfunction "1_1") (pintype "passive"))
      (node (ref "VD5") (pin "3") (pinfunction "3_3") (pintype "passive"))
    )
    (net (code "36") (name "Net-(C18-Pad1)") (class "Default")
      (node (ref "C18") (pin "1") (pintype "passive"))
      (node (ref "R10") (pin "1") (pinfunction "1_1") (pintype "passive"))
      (node (ref "R9") (pin "2") (pinfunction "2_2") (pintype "passive"))
    )
    (net (code "37") (name "Net-(C24-Pad2)") (class "Default")
      (node (ref "C24") (pin "2") (pintype "passive"))
      (node (ref "R14") (pin "1") (pinfunction "1_1") (pintype "passive"))
    )
    (net (code "38") (name "Net-(C29-Pad2)") (class "Default")
      (node (ref "C29") (pin "2") (pintype "passive"))
      (node (ref "R16") (pin "1") (pinfunction "1_1") (pintype "passive"))
    )
    (net (code "39") (name "Net-(C36-Pad2)") (class "Default")
      (node (ref "C36") (pin "2") (pintype "passive"))
      (node (ref "R23") (pin "2") (pinfunction "2_2") (pintype "passive"))
      (node (ref "R24") (pin "1") (pinfunction "1_1") (pintype "passive"))
    )
    (net (code "40") (name "Net-(C37-Pad2)") (class "Default")
      (node (ref "C37") (pin "2") (pintype "passive"))
      (node (ref "R21") (pin "1") (pinfunction "1_1") (pintype "passive"))
    )
    (net (code "41") (name "Net-(DA1-ADJ)") (class "Default")
      (node (ref "DA1") (pin "1") (pinfunction "ADJ_1") (pintype "power_in"))
      (node (ref "R2") (pin "2") (pinfunction "2_2") (pintype "passive"))
      (node (ref "R3") (pin "1") (pinfunction "1_1") (pintype "passive"))
    )
    (net (code "42") (name "Net-(DA1-OUT)") (class "Default")
      (node (ref "DA1") (pin "2") (pinfunction "OUT_2") (pintype "power_in"))
      (node (ref "DA1") (pin "4") (pinfunction "TAB_4") (pintype "power_in"))
      (node (ref "R1") (pin "2") (pinfunction "2_2") (pintype "passive"))
      (node (ref "VD1") (pin "2") (pintype "passive"))
      (node (ref "VT1") (pin "1") (pinfunction "G_1") (pintype "passive"))
    )
    (net (code "43") (name "Net-(DA2A-IN+)") (class "Default")
      (node (ref "C35") (pin "2") (pintype "passive"))
      (node (ref "DA2") (pin "3") (pinfunction "IN+_3") (pintype "passive"))
      (node (ref "DA2") (pin "5") (pinfunction "IN+_5") (pintype "passive"))
      (node (ref "DA3") (pin "3") (pinfunction "IN+_3") (pintype "passive"))
      (node (ref "DA3") (pin "5") (pinfunction "IN+_5") (pintype "passive"))
      (node (ref "R22") (pin "2") (pinfunction "2_2") (pintype "passive"))
      (node (ref "R23") (pin "1") (pinfunction "1_1") (pintype "passive"))
    )
    (net (code "44") (name "Net-(DA2A-IN-)") (class "Default")
      (node (ref "C20") (pin "2") (pintype "passive"))
      (node (ref "C23") (pin "1") (pintype "passive"))
      (node (ref "DA2") (pin "2") (pinfunction "IN-_2") (pintype "passive"))
      (node (ref "R13") (pin "1") (pinfunction "1_1") (pintype "passive"))
    )
    (net (code "45") (name "Net-(DA2A-OUT)") (class "Default")
      (node (ref "C23") (pin "2") (pintype "passive"))
      (node (ref "C24") (pin "1") (pintype "passive"))
      (node (ref "DA2") (pin "1") (pinfunction "OUT_1") (pintype "passive"))
      (node (ref "R13") (pin "2") (pinfunction "2_2") (pintype "passive"))
    )
    (net (code "46") (name "Net-(DA2B-IN-)") (class "Default")
      (node (ref "C27") (pin "1") (pintype "passive"))
      (node (ref "DA2") (pin "6") (pinfunction "IN-_6") (pintype "passive"))
      (node (ref "R14") (pin "2") (pinfunction "2_2") (pintype "passive"))
      (node (ref "R15") (pin "1") (pinfunction "1_1") (pintype "passive"))
    )
    (net (code "47") (name "Net-(DA2B-OUT)") (class "Default")
      (node (ref "C27") (pin "2") (pintype "passive"))
      (node (ref "C29") (pin "1") (pintype "passive"))
      (node (ref "DA2") (pin "7") (pinfunction "OUT_7") (pintype "passive"))
      (node (ref "R15") (pin "2") (pinfunction "2_2") (pintype "passive"))
    )
    (net (code "48") (name "Net-(DA3A-IN-)") (class "Default")
      (node (ref "C34") (pin "1") (pintype "passive"))
      (node (ref "DA3") (pin "2") (pinfunction "IN-_2") (pintype "passive"))
      (node (ref "R16") (pin "2") (pinfunction "2_2") (pintype "passive"))
      (node (ref "R19") (pin "1") (pinfunction "1_1") (pintype "passive"))
    )
    (net (code "49") (name "Net-(DA3A-OUT)") (class "Default")
      (node (ref "C34") (pin "2") (pintype "passive"))
      (node (ref "C37") (pin "1") (pintype "passive"))
      (node (ref "DA3") (pin "1") (pinfunction "OUT_1") (pintype "passive"))
      (node (ref "R19") (pin "2") (pinfunction "2_2") (pintype "passive"))
    )
    (net (code "50") (name "Net-(DA3B-IN-)") (class "Default")
      (node (ref "C38") (pin "1") (pintype "passive"))
      (node (ref "DA3") (pin "6") (pinfunction "IN-_6") (pintype "passive"))
      (node (ref "R21") (pin "2") (pinfunction "2_2") (pintype "passive"))
      (node (ref "R26") (pin "1") (pinfunction "1_1") (pintype "passive"))
    )
    (net (code "51") (name "Net-(DA3B-OUT)") (class "Default")
      (node (ref "C38") (pin "2") (pintype "passive"))
      (node (ref "DA3") (pin "7") (pinfunction "OUT_7") (pintype "passive"))
      (node (ref "DA4") (pin "4") (pinfunction "IN-_4") (pintype "passive"))
      (node (ref "R26") (pin "2") (pinfunction "2_2") (pintype "passive"))
    )
    (net (code "52") (name "Net-(DA4A-IN+)") (class "Default")
      (node (ref "DA4") (pin "3") (pinfunction "IN+_3") (pintype "passive"))
      (node (ref "R23") (pin "3") (pinfunction "3_3") (pintype "passive"))
    )
    (net (code "53") (name "Net-(DD1-CBUS0)") (class "Default")
      (node (ref "DD1") (pin "23") (pinfunction "CBUS0_23") (pintype "passive"))
      (node (ref "VD6") (pin "1") (pinfunction "K_1") (pintype "passive"))
    )
    (net (code "54") (name "Net-(DD1-CBUS1)") (class "Default")
      (node (ref "DD1") (pin "22") (pinfunction "CBUS1_22") (pintype "passive"))
      (node (ref "VD7") (pin "1") (pinfunction "K_1") (pintype "passive"))
    )
    (net (code "55") (name "Net-(DD1-USBDM)") (class "Default")
      (node (ref "DD1") (pin "16") (pinfunction "USBDM_16") (pintype "passive"))
      (node (ref "R4") (pin "2") (pinfunction "2_2") (pintype "passive"))
    )
    (net (code "56") (name "Net-(DD1-USBDP)") (class "Default")
      (node (ref "DD1") (pin "15") (pinfunction "USBDP_15") (pintype "passive"))
      (node (ref "R5") (pin "2") (pinfunction "2_2") (pintype "passive"))
    )
    (net (code "57") (name "Net-(DD1-~{DTR})") (class "Default")
      (node (ref "C14") (pin "2") (pintype "passive"))
      (node (ref "DD1") (pin "2") (pinfunction "~{DTR}_2") (pintype "passive"))
    )
    (net (code "58") (name "Net-(DD1-~{RESET})") (class "Default")
      (node (ref "DD1") (pin "19") (pinfunction "~{RESET}_19") (pintype "passive"))
      (node (ref "R6") (pin "2") (pinfunction "2_2") (pintype "passive"))
    )
    (net (code "59") (name "Net-(DD2-PB6{slash}PCINT6{slash}XTAL1{slash}TOSC1)") (class "Default")
      (node (ref "C17") (pin "1") (pintype "passive"))
      (node (ref "DD2") (pin "7") (pinfunction "PB6/PCINT6/XTAL1/TOSC1_7") (pintype "passive"))
      (node (ref "ZQ1") (pin "1") (pintype "passive"))
    )
    (net (code "60") (name "Net-(DD2-PB7{slash}PCINT7{slash}XTAL2{slash}TOSC2)") (class "Default")
      (node (ref "C19") (pin "1") (pintype "passive"))
      (node (ref "DD2") (pin "8") (pinfunction "PB7/PCINT7/XTAL2/TOSC2_8") (pintype "passive"))
      (node (ref "ZQ1") (pin "3") (pintype "passive"))
    )
    (net (code "61") (name "Net-(R12-Pad2)") (class "Default")
      (node (ref "R12") (pin "2") (pinfunction "2_2") (pintype "passive"))
      (node (ref "SW1") (pin "2") (pintype "passive"))
    )
    (net (code "62") (name "Net-(VD6-A)") (class "Default")
      (node (ref "R7") (pin "1") (pinfunction "1_1") (pintype "passive"))
      (node (ref "VD6") (pin "2") (pinfunction "A_2") (pintype "passive"))
    )
    (net (code "63") (name "Net-(VD7-A)") (class "Default")
      (node (ref "R8") (pin "1") (pinfunction "1_1") (pintype "passive"))
      (node (ref "VD7") (pin "2") (pinfunction "A_2") (pintype "passive"))
    )
    (net (code "64") (name "Net-(VD10-K)") (class "Default")
      (node (ref "C20") (pin "1") (pintype "passive"))
      (node (ref "R10") (pin "2") (pinfunction "2_2") (pintype "passive"))
      (node (ref "VD10") (pin "1") (pinfunction "K_1") (pintype "passive"))
      (node (ref "VD8") (pin "1") (pinfunction "K_1") (pintype "passive"))
      (node (ref "VD9") (pin "1") (pinfunction "K_1") (pintype "passive"))
    )
    (net (code "65") (name "Net-(VD11-A)") (class "Default")
      (node (ref "R20") (pin "1") (pinfunction "1_1") (pintype "passive"))
      (node (ref "VD11") (pin "2") (pinfunction "A_2") (pintype "passive"))
    )
    (net (code "66") (name "Net-(VD12-A)") (class "Default")
      (node (ref "R25") (pin "1") (pinfunction "1_1") (pintype "passive"))
      (node (ref "VD12") (pin "2") (pinfunction "A_2") (pintype "passive"))
    )
    (net (code "67") (name "Net-(VT1-D)") (class "Default")
      (node (ref "VD2") (pin "2") (pintype "passive"))
      (node (ref "VT1") (pin "3") (pinfunction "D_3") (pintype "passive"))
    )
    (net (code "68") (name "Net-(X1-+V)") (class "Default")
      (node (ref "FU1") (pin "1") (pinfunction "1_1") (pintype "passive"))
      (node (ref "X1") (pin "1") (pinfunction "+V_1") (pintype "passive"))
    )
    (net (code "69") (name "Net-(X1-DM)") (class "Default")
      (node (ref "C5") (pin "1") (pintype "passive"))
      (node (ref "R4") (pin "1") (pinfunction "1_1") (pintype "passive"))
      (node (ref "VD3") (pin "1") (pintype "passive"))
      (node (ref "VD3") (pin "6") (pintype "passive"))
      (node (ref "X1") (pin "2") (pinfunction "DM_2") (pintype "passive"))
    )
    (net (code "70") (name "Net-(X1-DP)") (class "Default")
      (node (ref "C8") (pin "1") (pintype "passive"))
      (node (ref "R5") (pin "1") (pinfunction "1_1") (pintype "passive"))
      (node (ref "VD3") (pin "3") (pintype "passive"))
      (node (ref "VD3") (pin "4") (pintype "passive"))
      (node (ref "X1") (pin "3") (pinfunction "DP_3") (pintype "passive"))
    )
    (net (code "71") (name "SHIELD") (class "Default")
      (node (ref "VD3") (pin "2") (pintype "passive"))
      (node (ref "X1") (pin "6") (pinfunction "SHIELD_6") (pintype "passive"))
    )
    (net (code "72") (name "VCCP") (class "Default")
      (node (ref "C30") (pin "2") (pintype "passive"))
      (node (ref "C32") (pin "2") (pintype "passive"))
      (node (ref "C33") (pin "1") (pintype "passive"))
      (node (ref "DD2") (pin "18") (pinfunction "AVCC_18") (pintype "passive"))
      (node (ref "DD2") (pin "4") (pinfunction "VCC_4") (pintype "passive"))
      (node (ref "DD2") (pin "6") (pinfunction "VCC_6") (pintype "passive"))
      (node (ref "L3") (pin "2") (pintype "passive"))
      (node (ref "R11") (pin "1") (pinfunction "1_1") (pintype "passive"))
      (node (ref "R20") (pin "2") (pinfunction "2_2") (pintype "passive"))
    )
    (net (code "73") (name "VIN") (class "Default")
      (node (ref "C1") (pin "1") (pintype "passive"))
      (node (ref "C2") (pin "2") (pintype "passive"))
      (node (ref "DA1") (pin "3") (pinfunction "IN_3") (pintype "power_in"))
      (node (ref "X3") (pin "1") (pinfunction "1_1") (pintype "passive"))
    )
    (net (code "74") (name "VUSB") (class "Default")
      (node (ref "C7") (pin "1") (pintype "passive"))
      (node (ref "C9") (pin "2") (pintype "passive"))
      (node (ref "DD1") (pin "20") (pinfunction "VCC_20") (pintype "passive"))
      (node (ref "DD1") (pin "4") (pinfunction "VCCIO_4") (pintype "passive"))
      (node (ref "L1") (pin "1") (pintype "passive"))
      (node (ref "R6") (pin "1") (pinfunction "1_1") (pintype "passive"))
      (node (ref "R7") (pin "2") (pinfunction "2_2") (pintype "passive"))
      (node (ref "R8") (pin "2") (pinfunction "2_2") (pintype "passive"))
      (node (ref "VT1") (pin "2") (pinfunction "S_2") (pintype "passive"))
    )
    (net (code "75") (name "unconnected-(DD1-CBUS2-Pad13)") (class "Default")
      (node (ref "DD1") (pin "13") (pinfunction "CBUS2_13") (pintype "passive"))
    )
    (net (code "76") (name "unconnected-(DD1-CBUS3-Pad14)") (class "Default")
      (node (ref "DD1") (pin "14") (pinfunction "CBUS3_14") (pintype "passive"))
    )
    (net (code "77") (name "unconnected-(DD1-CBUS4-Pad12)") (class "Default")
      (node (ref "DD1") (pin "12") (pinfunction "CBUS4_12") (pintype "passive"))
    )
    (net (code "78") (name "unconnected-(DD1-OSCI-Pad27)") (class "Default")
      (node (ref "DD1") (pin "27") (pinfunction "OSCI_27") (pintype "passive"))
    )
    (net (code "79") (name "unconnected-(DD1-OSCO-Pad28)") (class "Default")
      (node (ref "DD1") (pin "28") (pinfunction "OSCO_28") (pintype "passive"))
    )
    (net (code "80") (name "unconnected-(DD1-~{CTS}-Pad11)") (class "Default")
      (node (ref "DD1") (pin "11") (pinfunction "~{CTS}_11") (pintype "passive"))
    )
    (net (code "81") (name "unconnected-(DD1-~{DCD}-Pad10)") (class "Default")
      (node (ref "DD1") (pin "10") (pinfunction "~{DCD}_10") (pintype "passive"))
    )
    (net (code "82") (name "unconnected-(DD1-~{DSR}-Pad9)") (class "Default")
      (node (ref "DD1") (pin "9") (pinfunction "~{DSR}_9") (pintype "passive"))
    )
    (net (code "83") (name "unconnected-(DD1-~{RI}-Pad6)") (class "Default")
      (node (ref "DD1") (pin "6") (pinfunction "~{RI}_6") (pintype "passive"))
    )
    (net (code "84") (name "unconnected-(DD1-~{RTS}-Pad3)") (class "Default")
      (node (ref "DD1") (pin "3") (pinfunction "~{RTS}_3") (pintype "passive"))
    )
    (net (code "85") (name "unconnected-(X1-ID-Pad4)") (class "Default")
      (node (ref "X1") (pin "4") (pinfunction "ID_4") (pintype "passive"))
    )
  )
)
